# Analog_Front_End.net
KiCad netlist of a schematic drawn in Altium Designer
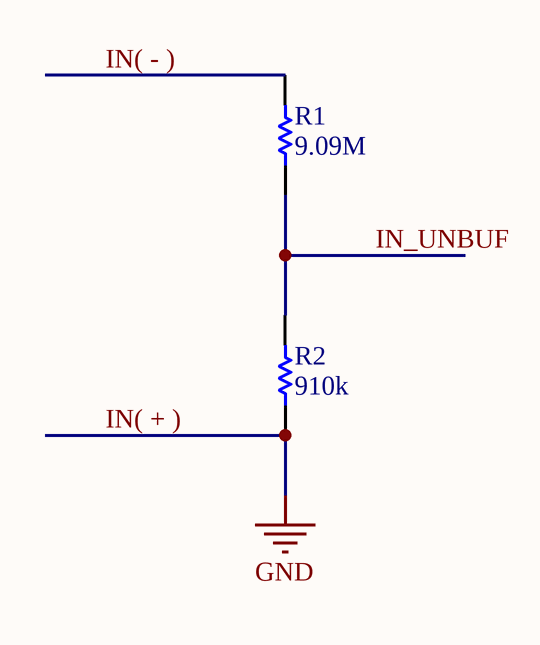
[diagram p0: Analog_Front_End.SchDoc]

(export (version "E")
  (design (tool "Eeschema 10.0.6"))
  (components
    (comp (ref "R1")
      (value "9.09M")
      (footprint "RESC_0603[0201]_N")
      (description "RES SMD 9.09M OHM 1% 1/10W 0603")
      (fields
        (field (name "MANUFACTURER") "Vishay Dale")
        (field (name "MANUFACTURER PART NUMBER") "CRCW06039M09FKEA")
      )
      (libsource (lib "mechanart_oshw") (part "ResSMT"))
    )
    (comp (ref "R2")
      (value "910k")
      (footprint "RESC_0603[0201]_N")
      (description "RES SMD 910K OHM 1% 1/10W 0603")
      (fields
        (field (name "MANUFACTURER") "Vishay Dale")
        (field (name "MANUFACTURER PART NUMBER") "CRCW0603910KFKEA")
      )
      (libsource (lib "mechanart_oshw") (part "ResSMT"))
    )
  )
  (nets
    (net (code "1") (name "/IN( - )") (class "Default")
      (node (ref "R1") (pin "2") (pinfunction "2_2") (pintype "passive"))
    )
    (net (code "2") (name "/IN_UNBUF") (class "Default")
      (node (ref "R1") (pin "1") (pinfunction "1_1") (pintype "passive"))
      (node (ref "R2") (pin "2") (pinfunction "2_2") (pintype "passive"))
    )
    (net (code "3") (name "GND") (class "Default")
      (node (ref "R2") (pin "1") (pinfunction "1_1") (pintype "passive"))
    )
  )
)
